# Ethernet.net
KiCad netlist of a schematic drawn in Altium Designer
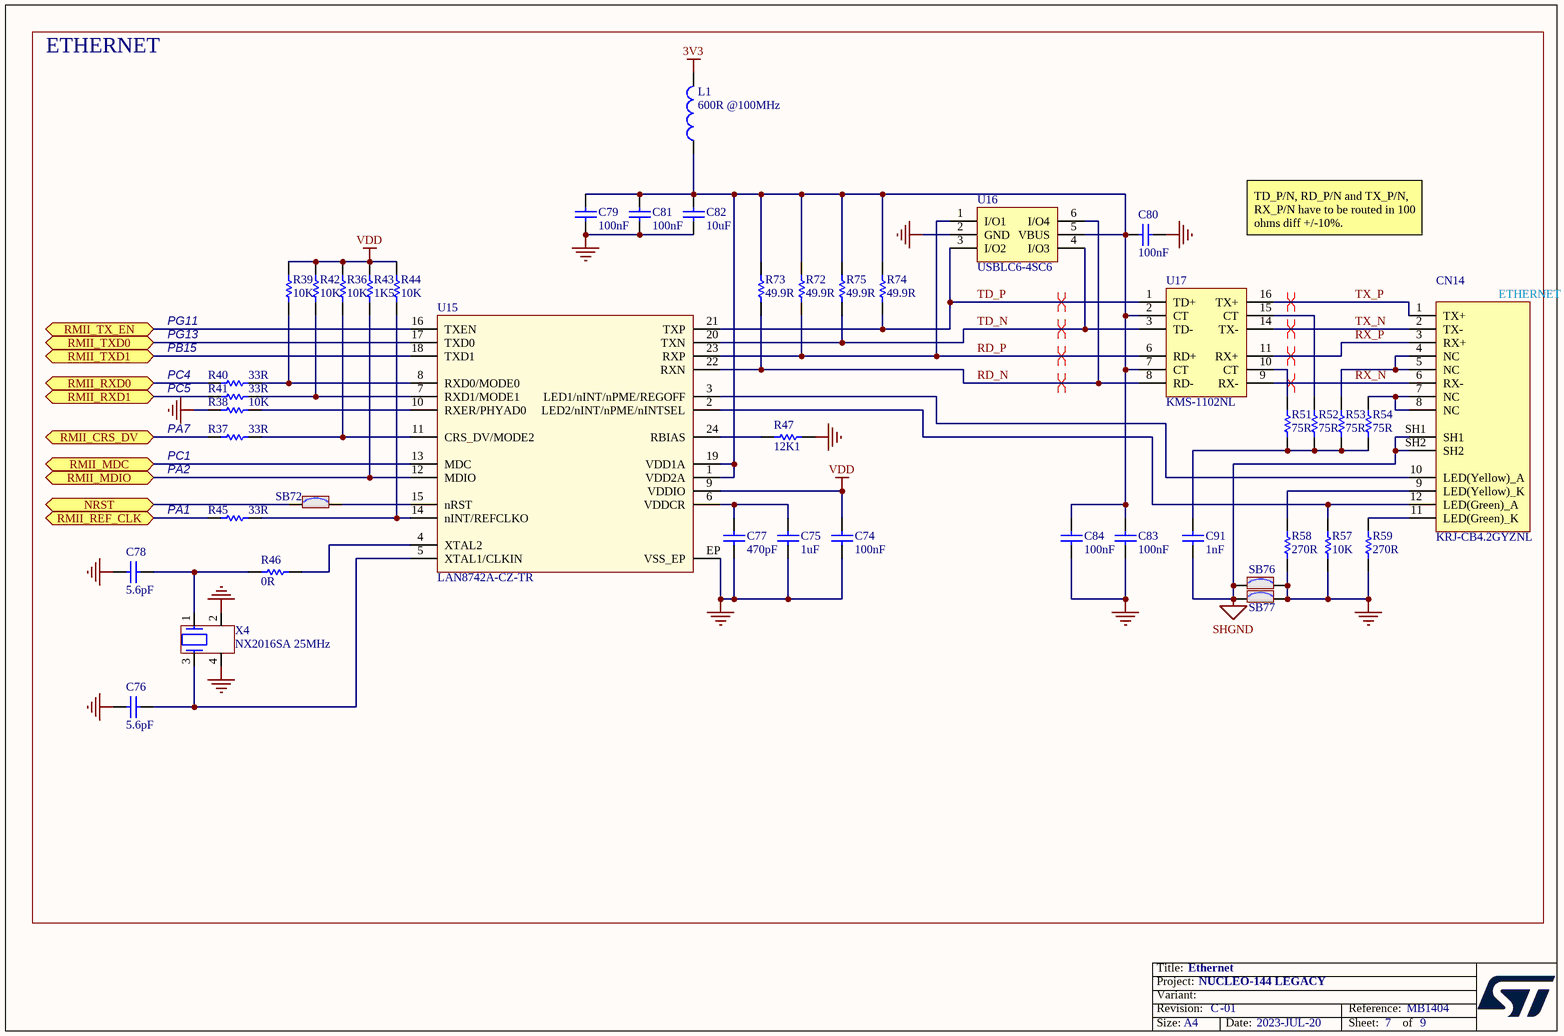
[diagram p0: Ethernet.SchDoc]

(export (version "E")
  (design (tool "Eeschema 10.0.6"))
  (components
    (comp (ref "C74")
      (value "100nF")
      (footprint "C0603")
      (description "Capacitor, MLCC, 100nF, 6V3, X5R, +/-10%, 0603, T=0.8mm")
      (fields (field (name "INTERNAL_PART_NUMBER") "MCD-02119") (field (name "MANUFACTURER") "KEMET"))
      (libsource (lib "MCD_PARTS_database") (part "Capacitor"))
    )
    (comp (ref "C75")
      (value "1uF")
      (footprint "MCD_PARTS:C0402")
      (description "Capacitor, MLCC, 1uF, 6V3, X5R, 10%, 0402, T=0,5mm")
      (fields
        (field (name "INTERNAL_PART_NUMBER") "MCD-00095")
        (field (name "MANUFACTURER_PART_NUMBER") "GRM155R61E105KA12")
        (field (name "PROVIDED_BY") "SUBCO")
      )
      (libsource (lib "MCD_PARTS_database") (part "Capacitor"))
    )
    (comp (ref "C76")
      (value "5.6pF")
      (footprint "MCD_PARTS:C0402")
      (description "Capacitor, MLCC, 5.6pF, 50V, NPO, 5%, 0402, T=0,5mm")
      (fields
        (field (name "INTERNAL_PART_NUMBER") "MCD-01374")
        (field (name "MANUFACTURER_PART_NUMBER") "CC0402BRNPO9BN5R6")
        (field (name "PROVIDED_BY") "SUBCO")
      )
      (libsource (lib "MCD_PARTS_database") (part "Capacitor"))
    )
    (comp (ref "C77")
      (value "470pF")
      (footprint "MCD_PARTS:C0402")
      (description "Capacitor, MLCC, 470pF, 50V, NPO, 5%, 0402, T=0,5mm")
      (fields
        (field (name "INTERNAL_PART_NUMBER") "MCD-00724")
        (field (name "MANUFACTURER_PART_NUMBER") "CC0402JRNPO9BN471")
        (field (name "PROVIDED_BY") "SUBCO")
      )
      (libsource (lib "MCD_PARTS_database") (part "Capacitor"))
    )
    (comp (ref "C78")
      (value "5.6pF")
      (footprint "MCD_PARTS:C0402")
      (description "Capacitor, MLCC, 5.6pF, 50V, NPO, 5%, 0402, T=0,5mm")
      (fields
        (field (name "INTERNAL_PART_NUMBER") "MCD-01374")
        (field (name "MANUFACTURER_PART_NUMBER") "CC0402BRNPO9BN5R6")
        (field (name "PROVIDED_BY") "SUBCO")
      )
      (libsource (lib "MCD_PARTS_database") (part "Capacitor"))
    )
    (comp (ref "C79")
      (value "100nF")
      (footprint "C0603")
      (description "Capacitor, MLCC, 100nF, 6V3, X5R, +/-10%, 0603, T=0.8mm")
      (fields (field (name "INTERNAL_PART_NUMBER") "MCD-02119") (field (name "MANUFACTURER") "KEMET"))
      (libsource (lib "MCD_PARTS_database") (part "Capacitor"))
    )
    (comp (ref "C80")
      (value "100nF")
      (footprint "C0603")
      (description "Capacitor, MLCC, 100nF, 6V3, X5R, +/-10%, 0603, T=0.8mm")
      (fields (field (name "INTERNAL_PART_NUMBER") "MCD-02119") (field (name "MANUFACTURER") "KEMET"))
      (libsource (lib "MCD_PARTS_database") (part "Capacitor"))
    )
    (comp (ref "C81")
      (value "100nF")
      (footprint "C0603")
      (description "Capacitor, MLCC, 100nF, 6V3, X5R, +/-10%, 0603, T=0.8mm")
      (fields (field (name "INTERNAL_PART_NUMBER") "MCD-02119") (field (name "MANUFACTURER") "KEMET"))
      (libsource (lib "MCD_PARTS_database") (part "Capacitor"))
    )
    (comp (ref "C82")
      (value "10uF")
      (footprint "MCD_PARTS:C0603")
      (description "Capacitor, MLCC, 10µF, 10V, X5R, 10%, 0603, T=0.8mm")
      (fields
        (field (name "INTERNAL_PART_NUMBER") "MCD-01124")
        (field (name "MANUFACTURER_PART_NUMBER") "GRM188R61A106KAAL")
        (field (name "PROVIDED_BY") "SUBCO")
      )
      (libsource (lib "MCD_PARTS_database") (part "Capacitor"))
    )
    (comp (ref "C83")
      (value "100nF")
      (footprint "C0603")
      (description "Capacitor, MLCC, 100nF, 6V3, X5R, +/-10%, 0603, T=0.8mm")
      (fields (field (name "INTERNAL_PART_NUMBER") "MCD-02119") (field (name "MANUFACTURER") "KEMET"))
      (libsource (lib "MCD_PARTS_database") (part "Capacitor"))
    )
    (comp (ref "C84")
      (value "100nF")
      (footprint "C0603")
      (description "Capacitor, MLCC, 100nF, 6V3, X5R, +/-10%, 0603, T=0.8mm")
      (fields (field (name "INTERNAL_PART_NUMBER") "MCD-02119") (field (name "MANUFACTURER") "KEMET"))
      (libsource (lib "MCD_PARTS_database") (part "Capacitor"))
    )
    (comp (ref "C91")
      (value "1nF")
      (footprint "MCD_PARTS:C1206_H1P6")
      (description "Capacitor, MLCC, 1nF, 2KV, X7R, 10%, 1206, T=1,25mm")
      (fields
        (field (name "INTERNAL_PART_NUMBER") "MCD-00722")
        (field (name "MANUFACTURER_PART_NUMBER") "CC1206KKX7RDBB102")
        (field (name "PROVIDED_BY") "SUBCO")
      )
      (libsource (lib "MCD_PARTS_database") (part "Capacitor"))
    )
    (comp (ref "CN14")
      (value "KRJ-CB4.2GYZNL")
      (footprint "MCD_PARTS:CON_RJ45_DGKYD_KRJ-CB4.2GYZNL")
      (description "RJ45 jack, single port, with LEDS, Metal shielded dip low profile")
      (fields
        (field (name "INTERNAL_PART_NUMBER") "MCD-00717")
        (field (name "MANUFACTURER") "DONGGUAN KEYOUDA ELECTRONIC TECHNOLOGY")
        (field (name "PROVIDED_BY") "SUBCO")
      )
      (libsource (lib "MCD_PARTS_database") (part "RJ45_KRJ-CB4.2GYZNL"))
    )
    (comp (ref "L1")
      (value "600R @100MHz")
      (footprint "MCD_PARTS:L0603")
      (description "Ferrite bead, 600R@100MHz, +/-25%, 500mA, 380mR, 0603, T=0.8mm")
      (fields (field (name "INTERNAL_PART_NUMBER") "MCD-02437") (field (name "MANUFACTURER") "MURATA"))
      (libsource (lib "MCD_PARTS_database") (part "BEAD"))
    )
    (comp (ref "R36")
      (value "10K")
      (footprint "MCD_PARTS:R0402")
      (description "Resistor,10K,0402,1%,1/16W")
      (fields
        (field (name "INTERNAL_PART_NUMBER") "MCD-00053")
        (field (name "MANUFACTURER_PART_NUMBER") "RC0402FR-0710KL")
        (field (name "PROVIDED_BY") "SUBCO")
      )
      (libsource (lib "MCD_PARTS_database") (part "Resistor"))
    )
    (comp (ref "R37")
      (value "33R")
      (footprint "MCD_PARTS:R0402")
      (description "Resistor,33R,0402,1%,1/16W")
      (fields
        (field (name "INTERNAL_PART_NUMBER") "MCD-00455")
        (field (name "MANUFACTURER_PART_NUMBER") "RC0402FR-0733RL")
        (field (name "PROVIDED_BY") "SUBCO")
      )
      (libsource (lib "MCD_PARTS_database") (part "Resistor"))
    )
    (comp (ref "R38")
      (value "10K")
      (footprint "MCD_PARTS:R0402")
      (description "Resistor,10K,0402,1%,1/16W")
      (fields
        (field (name "INTERNAL_PART_NUMBER") "MCD-00053")
        (field (name "MANUFACTURER_PART_NUMBER") "RC0402FR-0710KL")
        (field (name "PROVIDED_BY") "SUBCO")
      )
      (libsource (lib "MCD_PARTS_database") (part "Resistor"))
    )
    (comp (ref "R39")
      (value "10K")
      (footprint "MCD_PARTS:R0402")
      (description "Resistor,10K,0402,1%,1/16W")
      (fields
        (field (name "INTERNAL_PART_NUMBER") "MCD-00053")
        (field (name "MANUFACTURER_PART_NUMBER") "RC0402FR-0710KL")
        (field (name "PROVIDED_BY") "SUBCO")
      )
      (libsource (lib "MCD_PARTS_database") (part "Resistor"))
    )
    (comp (ref "R40")
      (value "33R")
      (footprint "MCD_PARTS:R0402")
      (description "Resistor,33R,0402,1%,1/16W")
      (fields
        (field (name "INTERNAL_PART_NUMBER") "MCD-00455")
        (field (name "MANUFACTURER_PART_NUMBER") "RC0402FR-0733RL")
        (field (name "PROVIDED_BY") "SUBCO")
      )
      (libsource (lib "MCD_PARTS_database") (part "Resistor"))
    )
    (comp (ref "R41")
      (value "33R")
      (footprint "MCD_PARTS:R0402")
      (description "Resistor,33R,0402,1%,1/16W")
      (fields
        (field (name "INTERNAL_PART_NUMBER") "MCD-00455")
        (field (name "MANUFACTURER_PART_NUMBER") "RC0402FR-0733RL")
        (field (name "PROVIDED_BY") "SUBCO")
      )
      (libsource (lib "MCD_PARTS_database") (part "Resistor"))
    )
    (comp (ref "R42")
      (value "10K")
      (footprint "MCD_PARTS:R0402")
      (description "Resistor,10K,0402,1%,1/16W")
      (fields
        (field (name "INTERNAL_PART_NUMBER") "MCD-00053")
        (field (name "MANUFACTURER_PART_NUMBER") "RC0402FR-0710KL")
        (field (name "PROVIDED_BY") "SUBCO")
      )
      (libsource (lib "MCD_PARTS_database") (part "Resistor"))
    )
    (comp (ref "R43")
      (value "1K5")
      (footprint "MCD_PARTS:R0402")
      (description "Resistor,1K5,0402,1%,1/16W")
      (fields
        (field (name "INTERNAL_PART_NUMBER") "MCD-00068")
        (field (name "MANUFACTURER_PART_NUMBER") "RC0402FR-071K5L")
        (field (name "PROVIDED_BY") "SUBCO")
      )
      (libsource (lib "MCD_PARTS_database") (part "Resistor"))
    )
    (comp (ref "R44")
      (value "10K")
      (footprint "MCD_PARTS:R0402")
      (description "Resistor,10K,0402,1%,1/16W")
      (fields
        (field (name "INTERNAL_PART_NUMBER") "MCD-00053")
        (field (name "MANUFACTURER_PART_NUMBER") "RC0402FR-0710KL")
        (field (name "PROVIDED_BY") "SUBCO")
      )
      (libsource (lib "MCD_PARTS_database") (part "Resistor"))
    )
    (comp (ref "R45")
      (value "33R")
      (footprint "MCD_PARTS:R0402")
      (description "Resistor,33R,0402,1%,1/16W")
      (fields
        (field (name "INTERNAL_PART_NUMBER") "MCD-00455")
        (field (name "MANUFACTURER_PART_NUMBER") "RC0402FR-0733RL")
        (field (name "PROVIDED_BY") "SUBCO")
      )
      (libsource (lib "MCD_PARTS_database") (part "Resistor"))
    )
    (comp (ref "R46")
      (value "0R")
      (footprint "MCD_PARTS:R0402")
      (description "Resistor,0R,0402,5%,1/16W")
      (fields
        (field (name "INTERNAL_PART_NUMBER") "MCD-00052")
        (field (name "MANUFACTURER_PART_NUMBER") "RC0402JR-070RL")
        (field (name "PROVIDED_BY") "SUBCO")
      )
      (libsource (lib "MCD_PARTS_database") (part "Resistor"))
    )
    (comp (ref "R47")
      (value "12K1")
      (footprint "MCD_PARTS:R0402")
      (description "Resistor,12K1,0402,1%,1/16W")
      (fields
        (field (name "INTERNAL_PART_NUMBER") "MCD-00723")
        (field (name "MANUFACTURER_PART_NUMBER") "RC0402FR-0712K1L")
        (field (name "PROVIDED_BY") "SUBCO")
      )
      (libsource (lib "MCD_PARTS_database") (part "Resistor"))
    )
    (comp (ref "R51")
      (value "75R")
      (footprint "MCD_PARTS:R0402")
      (description "Resistor,75R,0402,1%,1/16W")
      (fields
        (field (name "INTERNAL_PART_NUMBER") "MCD-00515")
        (field (name "MANUFACTURER_PART_NUMBER") "RC0402FR-0775RL")
        (field (name "PROVIDED_BY") "SUBCO")
      )
      (libsource (lib "MCD_PARTS_database") (part "Resistor"))
    )
    (comp (ref "R52")
      (value "75R")
      (footprint "MCD_PARTS:R0402")
      (description "Resistor,75R,0402,1%,1/16W")
      (fields
        (field (name "INTERNAL_PART_NUMBER") "MCD-00515")
        (field (name "MANUFACTURER_PART_NUMBER") "RC0402FR-0775RL")
        (field (name "PROVIDED_BY") "SUBCO")
      )
      (libsource (lib "MCD_PARTS_database") (part "Resistor"))
    )
    (comp (ref "R53")
      (value "75R")
      (footprint "MCD_PARTS:R0402")
      (description "Resistor,75R,0402,1%,1/16W")
      (fields
        (field (name "INTERNAL_PART_NUMBER") "MCD-00515")
        (field (name "MANUFACTURER_PART_NUMBER") "RC0402FR-0775RL")
        (field (name "PROVIDED_BY") "SUBCO")
      )
      (libsource (lib "MCD_PARTS_database") (part "Resistor"))
    )
    (comp (ref "R54")
      (value "75R")
      (footprint "MCD_PARTS:R0402")
      (description "Resistor,75R,0402,1%,1/16W")
      (fields
        (field (name "INTERNAL_PART_NUMBER") "MCD-00515")
        (field (name "MANUFACTURER_PART_NUMBER") "RC0402FR-0775RL")
        (field (name "PROVIDED_BY") "SUBCO")
      )
      (libsource (lib "MCD_PARTS_database") (part "Resistor"))
    )
    (comp (ref "R57")
      (value "10K")
      (footprint "MCD_PARTS:R0402")
      (description "Resistor,10K,0402,1%,1/16W")
      (fields
        (field (name "INTERNAL_PART_NUMBER") "MCD-00053")
        (field (name "MANUFACTURER_PART_NUMBER") "RC0402FR-0710KL")
        (field (name "PROVIDED_BY") "SUBCO")
      )
      (libsource (lib "MCD_PARTS_database") (part "Resistor"))
    )
    (comp (ref "R58")
      (value "270R")
      (footprint "MCD_PARTS:R0402")
      (description "Resistor,270R,0402,1%,1/16W")
      (fields
        (field (name "INTERNAL_PART_NUMBER") "MCD-00441")
        (field (name "MANUFACTURER_PART_NUMBER") "RC0402FR-07270RL")
        (field (name "PROVIDED_BY") "SUBCO")
      )
      (libsource (lib "MCD_PARTS_database") (part "Resistor"))
    )
    (comp (ref "R59")
      (value "270R")
      (footprint "MCD_PARTS:R0402")
      (description "Resistor,270R,0402,1%,1/16W")
      (fields
        (field (name "INTERNAL_PART_NUMBER") "MCD-00441")
        (field (name "MANUFACTURER_PART_NUMBER") "RC0402FR-07270RL")
        (field (name "PROVIDED_BY") "SUBCO")
      )
      (libsource (lib "MCD_PARTS_database") (part "Resistor"))
    )
    (comp (ref "R72")
      (value "49.9R")
      (footprint "MCD_PARTS:R0402")
      (description "Resistor,49R9,0402,1%,1/16W")
      (fields
        (field (name "INTERNAL_PART_NUMBER") "MCD-00565")
        (field (name "MANUFACTURER_PART_NUMBER") "RC0402FR-0749R9L")
        (field (name "PROVIDED_BY") "SUBCO")
      )
      (libsource (lib "MCD_PARTS_database") (part "Resistor"))
    )
    (comp (ref "R73")
      (value "49.9R")
      (footprint "MCD_PARTS:R0402")
      (description "Resistor,49R9,0402,1%,1/16W")
      (fields
        (field (name "INTERNAL_PART_NUMBER") "MCD-00565")
        (field (name "MANUFACTURER_PART_NUMBER") "RC0402FR-0749R9L")
        (field (name "PROVIDED_BY") "SUBCO")
      )
      (libsource (lib "MCD_PARTS_database") (part "Resistor"))
    )
    (comp (ref "R74")
      (value "49.9R")
      (footprint "MCD_PARTS:R0402")
      (description "Resistor,49R9,0402,1%,1/16W")
      (fields
        (field (name "INTERNAL_PART_NUMBER") "MCD-00565")
        (field (name "MANUFACTURER_PART_NUMBER") "RC0402FR-0749R9L")
        (field (name "PROVIDED_BY") "SUBCO")
      )
      (libsource (lib "MCD_PARTS_database") (part "Resistor"))
    )
    (comp (ref "R75")
      (value "49.9R")
      (footprint "MCD_PARTS:R0402")
      (description "Resistor,49R9,0402,1%,1/16W")
      (fields
        (field (name "INTERNAL_PART_NUMBER") "MCD-00565")
        (field (name "MANUFACTURER_PART_NUMBER") "RC0402FR-0749R9L")
        (field (name "PROVIDED_BY") "SUBCO")
      )
      (libsource (lib "MCD_PARTS_database") (part "Resistor"))
    )
    (comp (ref "SB72")
      (value "SB_ON")
      (footprint "MCD_PARTS:SOLDER-BRIDGE_R0603-0R")
      (description "Solder Bridge ON")
      (fields
        (field (name "INTERNAL_PART_NUMBER") "MCD-00071")
        (field (name "MANUFACTURER_PART_NUMBER") "RC0603JR-070RL")
        (field (name "PROVIDED_BY") "SUBCO")
      )
      (libsource (lib "MCD_PARTS_database") (part "SB_ON"))
    )
    (comp (ref "SB76")
      (value "SB_ON")
      (footprint "MCD_PARTS:SOLDER-BRIDGE_R0603-0R")
      (description "Solder Bridge ON")
      (fields
        (field (name "INTERNAL_PART_NUMBER") "MCD-00071")
        (field (name "MANUFACTURER_PART_NUMBER") "RC0603JR-070RL")
        (field (name "PROVIDED_BY") "SUBCO")
      )
      (libsource (lib "MCD_PARTS_database") (part "SB_ON"))
    )
    (comp (ref "SB77")
      (value "SB_ON")
      (footprint "MCD_PARTS:SOLDER-BRIDGE_R0603-0R")
      (description "Solder Bridge ON")
      (fields
        (field (name "INTERNAL_PART_NUMBER") "MCD-00071")
        (field (name "MANUFACTURER_PART_NUMBER") "RC0603JR-070RL")
        (field (name "PROVIDED_BY") "SUBCO")
      )
      (libsource (lib "MCD_PARTS_database") (part "SB_ON"))
    )
    (comp (ref "U15")
      (value "LAN8742A-CZ-TR")
      (footprint "MCD_PARTS:ICC_VQFN24-EPAD_4X4_P050")
      (description "10/100M RMII Ethernet transceiver")
      (fields
        (field (name "INTERNAL_PART_NUMBER") "MCD-00719")
        (field (name "MANUFACTURER") "MICROCHIP")
        (field (name "PROVIDED_BY") "SUBCO")
      )
      (libsource (lib "MCD_PARTS_database") (part "LAN8742A-CZ-TR"))
    )
    (comp (ref "U16")
      (value "USBLC6-4SC6")
      (footprint "MCD_PARTS:ESD_SOT23-6L")
      (description "Very low capacitance ESD protection , 4 lines")
      (fields
        (field (name "INTERNAL_PART_NUMBER") "MCD-00250")
        (field (name "MANUFACTURER") "STMICROELECTRONICS")
        (field (name "PROVIDED_BY") "SUBCO with ST control")
      )
      (libsource (lib "MCD_PARTS_database") (part "USBLC6-4SC6"))
    )
    (comp (ref "U17")
      (value "KMS-1102NL")
      (footprint "MCD_PARTS:TRS_DGKYD_KMS-1102NL")
      (description "Discrete Magnetic Transformer Module, 16 pins, SMT, 100 Base-TX")
      (fields
        (field (name "INTERNAL_PART_NUMBER") "MCD-00718")
        (field (name "MANUFACTURER") "DONGGUAN KEYOUDA ELECTRONIC TECHNOLOGY")
        (field (name "PROVIDED_BY") "SUBCO")
      )
      (libsource (lib "MCD_PARTS_database") (part "KMS-1102NL"))
    )
    (comp (ref "X4")
      (value "NX2016SA 25MHz")
      (footprint "MCD_PARTS:CRY_NX2016SA_4P")
      (description "Crystal 25MHz, 6pF, +-20ppm, 80ohms max, SMD")
      (fields
        (field (name "INTERNAL_PART_NUMBER") "MCD-01364")
        (field (name "MANUFACTURER_PART_NUMBER") "NX2016SA 25MHz EXS00A-CS11321")
        (field (name "PROVIDED_BY") "SUBCO")
      )
      (libsource (lib "MCD_PARTS_database") (part "XTAL_4_PINS"))
    )
  )
  (nets
    (net (code "1") (name "/NRST") (class "Default")
      (node (ref "SB72") (pin "1") (pinfunction "1_1") (pintype "passive"))
    )
    (net (code "2") (name "/RD_N") (class "Default")
      (node (ref "R73") (pin "1") (pinfunction "1_1") (pintype "passive"))
      (node (ref "U15") (pin "22") (pinfunction "RXN_22") (pintype "passive"))
      (node (ref "U16") (pin "6") (pinfunction "I/O4_6") (pintype "passive"))
      (node (ref "U17") (pin "8") (pinfunction "RD-_8") (pintype "passive"))
    )
    (net (code "3") (name "/RD_P") (class "Default")
      (node (ref "R72") (pin "1") (pinfunction "1_1") (pintype "passive"))
      (node (ref "U15") (pin "23") (pinfunction "RXP_23") (pintype "passive"))
      (node (ref "U16") (pin "1") (pinfunction "I/O1_1") (pintype "passive"))
      (node (ref "U17") (pin "6") (pinfunction "RD+_6") (pintype "passive"))
    )
    (net (code "4") (name "/RMII_CRS_DV") (class "Default")
      (node (ref "R37") (pin "1") (pinfunction "1_1") (pintype "passive"))
    )
    (net (code "5") (name "/RMII_MDC") (class "Default")
      (node (ref "U15") (pin "13") (pinfunction "MDC_13") (pintype "passive"))
    )
    (net (code "6") (name "/RMII_MDIO") (class "Default")
      (node (ref "R43") (pin "1") (pinfunction "1_1") (pintype "passive"))
      (node (ref "U15") (pin "12") (pinfunction "MDIO_12") (pintype "passive"))
    )
    (net (code "7") (name "/RMII_REF_CLK") (class "Default")
      (node (ref "R45") (pin "1") (pinfunction "1_1") (pintype "passive"))
    )
    (net (code "8") (name "/RMII_RXD0") (class "Default")
      (node (ref "R40") (pin "1") (pinfunction "1_1") (pintype "passive"))
    )
    (net (code "9") (name "/RMII_RXD1") (class "Default")
      (node (ref "R41") (pin "1") (pinfunction "1_1") (pintype "passive"))
    )
    (net (code "10") (name "/RMII_TXD0") (class "Default")
      (node (ref "U15") (pin "17") (pinfunction "TXD0_17") (pintype "passive"))
    )
    (net (code "11") (name "/RMII_TXD1") (class "Default")
      (node (ref "U15") (pin "18") (pinfunction "TXD1_18") (pintype "passive"))
    )
    (net (code "12") (name "/RMII_TX_EN") (class "Default")
      (node (ref "U15") (pin "16") (pinfunction "TXEN_16") (pintype "passive"))
    )
    (net (code "13") (name "/RX_N") (class "Default")
      (node (ref "CN14") (pin "6") (pinfunction "RX-_6") (pintype "passive"))
      (node (ref "U17") (pin "9") (pinfunction "RX-_9") (pintype "passive"))
    )
    (net (code "14") (name "/RX_P") (class "Default")
      (node (ref "CN14") (pin "3") (pinfunction "RX+_3") (pintype "passive"))
      (node (ref "U17") (pin "11") (pinfunction "RX+_11") (pintype "passive"))
    )
    (net (code "15") (name "/TD_N") (class "Default")
      (node (ref "R75") (pin "1") (pinfunction "1_1") (pintype "passive"))
      (node (ref "U15") (pin "20") (pinfunction "TXN_20") (pintype "passive"))
      (node (ref "U16") (pin "4") (pinfunction "I/O3_4") (pintype "passive"))
      (node (ref "U17") (pin "3") (pinfunction "TD-_3") (pintype "passive"))
    )
    (net (code "16") (name "/TD_P") (class "Default")
      (node (ref "R74") (pin "1") (pinfunction "1_1") (pintype "passive"))
      (node (ref "U15") (pin "21") (pinfunction "TXP_21") (pintype "passive"))
      (node (ref "U16") (pin "3") (pinfunction "I/O2_3") (pintype "passive"))
      (node (ref "U17") (pin "1") (pinfunction "TD+_1") (pintype "passive"))
    )
    (net (code "17") (name "/TX_N") (class "Default")
      (node (ref "CN14") (pin "2") (pinfunction "TX-_2") (pintype "passive"))
      (node (ref "U17") (pin "14") (pinfunction "TX-_14") (pintype "passive"))
    )
    (net (code "18") (name "/TX_P") (class "Default")
      (node (ref "CN14") (pin "1") (pinfunction "TX+_1") (pintype "passive"))
      (node (ref "U17") (pin "16") (pinfunction "TX+_16") (pintype "passive"))
    )
    (net (code "19") (name "3V3") (class "Default")
      (node (ref "L1") (pin "2") (pinfunction "2_2") (pintype "passive"))
    )
    (net (code "20") (name "GND") (class "Default")
      (node (ref "C74") (pin "1") (pinfunction "1_1") (pintype "passive"))
      (node (ref "C75") (pin "1") (pinfunction "1_1") (pintype "passive"))
      (node (ref "C76") (pin "1") (pinfunction "1_1") (pintype "passive"))
      (node (ref "C77") (pin "1") (pinfunction "1_1") (pintype "passive"))
      (node (ref "C78") (pin "1") (pinfunction "1_1") (pintype "passive"))
      (node (ref "C79") (pin "1") (pinfunction "1_1") (pintype "passive"))
      (node (ref "C80") (pin "1") (pinfunction "1_1") (pintype "passive"))
      (node (ref "C81") (pin "1") (pinfunction "1_1") (pintype "passive"))
      (node (ref "C82") (pin "1") (pinfunction "1_1") (pintype "passive"))
      (node (ref "C83") (pin "1") (pinfunction "1_1") (pintype "passive"))
      (node (ref "C84") (pin "1") (pinfunction "1_1") (pintype "passive"))
      (node (ref "R38") (pin "2") (pinfunction "2_2") (pintype "passive"))
      (node (ref "R47") (pin "2") (pinfunction "2_2") (pintype "passive"))
      (node (ref "R57") (pin "1") (pinfunction "1_1") (pintype "passive"))
      (node (ref "R58") (pin "1") (pinfunction "1_1") (pintype "passive"))
      (node (ref "R59") (pin "1") (pinfunction "1_1") (pintype "passive"))
      (node (ref "SB76") (pin "2") (pinfunction "2_2") (pintype "passive"))
      (node (ref "SB77") (pin "2") (pinfunction "2_2") (pintype "passive"))
      (node (ref "U15") (pin "EP") (pinfunction "VSS_EP_EP") (pintype "passive"))
      (node (ref "U16") (pin "2") (pinfunction "GND_2") (pintype "passive"))
      (node (ref "X4") (pin "2") (pinfunction "2_2") (pintype "passive"))
      (node (ref "X4") (pin "4") (pinfunction "4_4") (pintype "passive"))
    )
    (net (code "21") (name "Net-(C78-Pad2)") (class "Default")
      (node (ref "C78") (pin "2") (pinfunction "2_2") (pintype "passive"))
      (node (ref "R46") (pin "1") (pinfunction "1_1") (pintype "passive"))
      (node (ref "X4") (pin "1") (pinfunction "1_1") (pintype "passive"))
    )
    (net (code "22") (name "Net-(C91-Pad2)") (class "Default")
      (node (ref "C91") (pin "2") (pinfunction "2_2") (pintype "passive"))
      (node (ref "R51") (pin "1") (pinfunction "1_1") (pintype "passive"))
      (node (ref "R52") (pin "1") (pinfunction "1_1") (pintype "passive"))
      (node (ref "R53") (pin "1") (pinfunction "1_1") (pintype "passive"))
      (node (ref "R54") (pin "1") (pinfunction "1_1") (pintype "passive"))
    )
    (net (code "23") (name "Net-(CN14-LED(Green)_A)") (class "Default")
      (node (ref "CN14") (pin "12") (pinfunction "LED(Green)_A_12") (pintype "passive"))
      (node (ref "R57") (pin "2") (pinfunction "2_2") (pintype "passive"))
      (node (ref "U15") (pin "2") (pinfunction "LED2/nINT/nPME/nINTSEL_2") (pintype "passive"))
    )
    (net (code "24") (name "Net-(CN14-LED(Green)_K)") (class "Default")
      (node (ref "CN14") (pin "11") (pinfunction "LED(Green)_K_11") (pintype "passive"))
      (node (ref "R59") (pin "2") (pinfunction "2_2") (pintype "passive"))
    )
    (net (code "25") (name "Net-(CN14-LED(Yellow)_A)") (class "Default")
      (node (ref "CN14") (pin "10") (pinfunction "LED(Yellow)_A_10") (pintype "passive"))
      (node (ref "U15") (pin "3") (pinfunction "LED1/nINT/nPME/REGOFF_3") (pintype "passive"))
    )
    (net (code "26") (name "Net-(CN14-LED(Yellow)_K)") (class "Default")
      (node (ref "CN14") (pin "9") (pinfunction "LED(Yellow)_K_9") (pintype "passive"))
      (node (ref "R58") (pin "2") (pinfunction "2_2") (pintype "passive"))
    )
    (net (code "27") (name "Net-(CN14-NC-Pad4)") (class "Default")
      (node (ref "CN14") (pin "4") (pinfunction "NC_4") (pintype "passive"))
      (node (ref "CN14") (pin "5") (pinfunction "NC_5") (pintype "passive"))
      (node (ref "R53") (pin "2") (pinfunction "2_2") (pintype "passive"))
    )
    (net (code "28") (name "Net-(CN14-NC-Pad7)") (class "Default")
      (node (ref "CN14") (pin "7") (pinfunction "NC_7") (pintype "passive"))
      (node (ref "CN14") (pin "8") (pinfunction "NC_8") (pintype "passive"))
      (node (ref "R54") (pin "2") (pinfunction "2_2") (pintype "passive"))
    )
    (net (code "29") (name "Net-(R51-Pad2)") (class "Default")
      (node (ref "R51") (pin "2") (pinfunction "2_2") (pintype "passive"))
      (node (ref "U17") (pin "10") (pinfunction "CT_10") (pintype "passive"))
    )
    (net (code "30") (name "Net-(R52-Pad2)") (class "Default")
      (node (ref "R52") (pin "2") (pinfunction "2_2") (pintype "passive"))
      (node (ref "U17") (pin "15") (pinfunction "CT_15") (pintype "passive"))
    )
    (net (code "31") (name "Net-(U15-CRS_DV{slash}MODE2)") (class "Default")
      (node (ref "R36") (pin "1") (pinfunction "1_1") (pintype "passive"))
      (node (ref "R37") (pin "2") (pinfunction "2_2") (pintype "passive"))
      (node (ref "U15") (pin "11") (pinfunction "CRS_DV/MODE2_11") (pintype "passive"))
    )
    (net (code "32") (name "Net-(U15-RBIAS)") (class "Default")
      (node (ref "R47") (pin "1") (pinfunction "1_1") (pintype "passive"))
      (node (ref "U15") (pin "24") (pinfunction "RBIAS_24") (pintype "passive"))
    )
    (net (code "33") (name "Net-(U15-RXD0{slash}MODE0)") (class "Default")
      (node (ref "R39") (pin "1") (pinfunction "1_1") (pintype "passive"))
      (node (ref "R40") (pin "2") (pinfunction "2_2") (pintype "passive"))
      (node (ref "U15") (pin "8") (pinfunction "RXD0/MODE0_8") (pintype "passive"))
    )
    (net (code "34") (name "Net-(U15-RXD1{slash}MODE1)") (class "Default")
      (node (ref "R41") (pin "2") (pinfunction "2_2") (pintype "passive"))
      (node (ref "R42") (pin "1") (pinfunction "1_1") (pintype "passive"))
      (node (ref "U15") (pin "7") (pinfunction "RXD1/MODE1_7") (pintype "passive"))
    )
    (net (code "35") (name "Net-(U15-RXER{slash}PHYAD0)") (class "Default")
      (node (ref "R38") (pin "1") (pinfunction "1_1") (pintype "passive"))
      (node (ref "U15") (pin "10") (pinfunction "RXER/PHYAD0_10") (pintype "passive"))
    )
    (net (code "36") (name "Net-(U15-VDD1A)") (class "Default")
      (node (ref "C79") (pin "2") (pinfunction "2_2") (pintype "passive"))
      (node (ref "C80") (pin "2") (pinfunction "2_2") (pintype "passive"))
      (node (ref "C81") (pin "2") (pinfunction "2_2") (pintype "passive"))
      (node (ref "C82") (pin "2") (pinfunction "2_2") (pintype "passive"))
      (node (ref "C83") (pin "2") (pinfunction "2_2") (pintype "passive"))
      (node (ref "C84") (pin "2") (pinfunction "2_2") (pintype "passive"))
      (node (ref "L1") (pin "1") (pinfunction "1_1") (pintype "passive"))
      (node (ref "R72") (pin "2") (pinfunction "2_2") (pintype "passive"))
      (node (ref "R73") (pin "2") (pinfunction "2_2") (pintype "passive"))
      (node (ref "R74") (pin "2") (pinfunction "2_2") (pintype "passive"))
      (node (ref "R75") (pin "2") (pinfunction "2_2") (pintype "passive"))
      (node (ref "U15") (pin "1") (pinfunction "VDD2A_1") (pintype "passive"))
      (node (ref "U15") (pin "19") (pinfunction "VDD1A_19") (pintype "passive"))
      (node (ref "U16") (pin "5") (pinfunction "VBUS_5") (pintype "passive"))
      (node (ref "U17") (pin "2") (pinfunction "CT_2") (pintype "passive"))
      (node (ref "U17") (pin "7") (pinfunction "CT_7") (pintype "passive"))
    )
    (net (code "37") (name "Net-(U15-VDDCR)") (class "Default")
      (node (ref "C75") (pin "2") (pinfunction "2_2") (pintype "passive"))
      (node (ref "C77") (pin "2") (pinfunction "2_2") (pintype "passive"))
      (node (ref "U15") (pin "6") (pinfunction "VDDCR_6") (pintype "passive"))
    )
    (net (code "38") (name "Net-(U15-XTAL1{slash}CLKIN)") (class "Default")
      (node (ref "C76") (pin "2") (pinfunction "2_2") (pintype "passive"))
      (node (ref "U15") (pin "5") (pinfunction "XTAL1/CLKIN_5") (pintype "passive"))
      (node (ref "X4") (pin "3") (pinfunction "3_3") (pintype "passive"))
    )
    (net (code "39") (name "Net-(U15-XTAL2)") (class "Default")
      (node (ref "R46") (pin "2") (pinfunction "2_2") (pintype "passive"))
      (node (ref "U15") (pin "4") (pinfunction "XTAL2_4") (pintype "passive"))
    )
    (net (code "40") (name "Net-(U15-nINT{slash}REFCLKO)") (class "Default")
      (node (ref "R44") (pin "1") (pinfunction "1_1") (pintype "passive"))
      (node (ref "R45") (pin "2") (pinfunction "2_2") (pintype "passive"))
      (node (ref "U15") (pin "14") (pinfunction "nINT/REFCLKO_14") (pintype "passive"))
    )
    (net (code "41") (name "Net-(U15-nRST)") (class "Default")
      (node (ref "SB72") (pin "2") (pinfunction "2_2") (pintype "passive"))
      (node (ref "U15") (pin "15") (pinfunction "nRST_15") (pintype "passive"))
    )
    (net (code "42") (name "SHGND") (class "Default")
      (node (ref "C91") (pin "1") (pinfunction "1_1") (pintype "passive"))
      (node (ref "CN14") (pin "SH1") (pinfunction "SH1_SH1") (pintype "passive"))
      (node (ref "CN14") (pin "SH2") (pinfunction "SH2_SH2") (pintype "passive"))
      (node (ref "SB76") (pin "1") (pinfunction "1_1") (pintype "passive"))
      (node (ref "SB77") (pin "1") (pinfunction "1_1") (pintype "passive"))
    )
    (net (code "43") (name "VDD") (class "Default")
      (node (ref "C74") (pin "2") (pinfunction "2_2") (pintype "passive"))
      (node (ref "R36") (pin "2") (pinfunction "2_2") (pintype "passive"))
      (node (ref "R39") (pin "2") (pinfunction "2_2") (pintype "passive"))
      (node (ref "R42") (pin "2") (pinfunction "2_2") (pintype "passive"))
      (node (ref "R43") (pin "2") (pinfunction "2_2") (pintype "passive"))
      (node (ref "R44") (pin "2") (pinfunction "2_2") (pintype "passive"))
      (node (ref "U15") (pin "9") (pinfunction "VDDIO_9") (pintype "passive"))
    )
  )
)
